# RiskChemi_Monitor_V1_05M1.net
KiCad netlist of a schematic drawn in Altium Designer
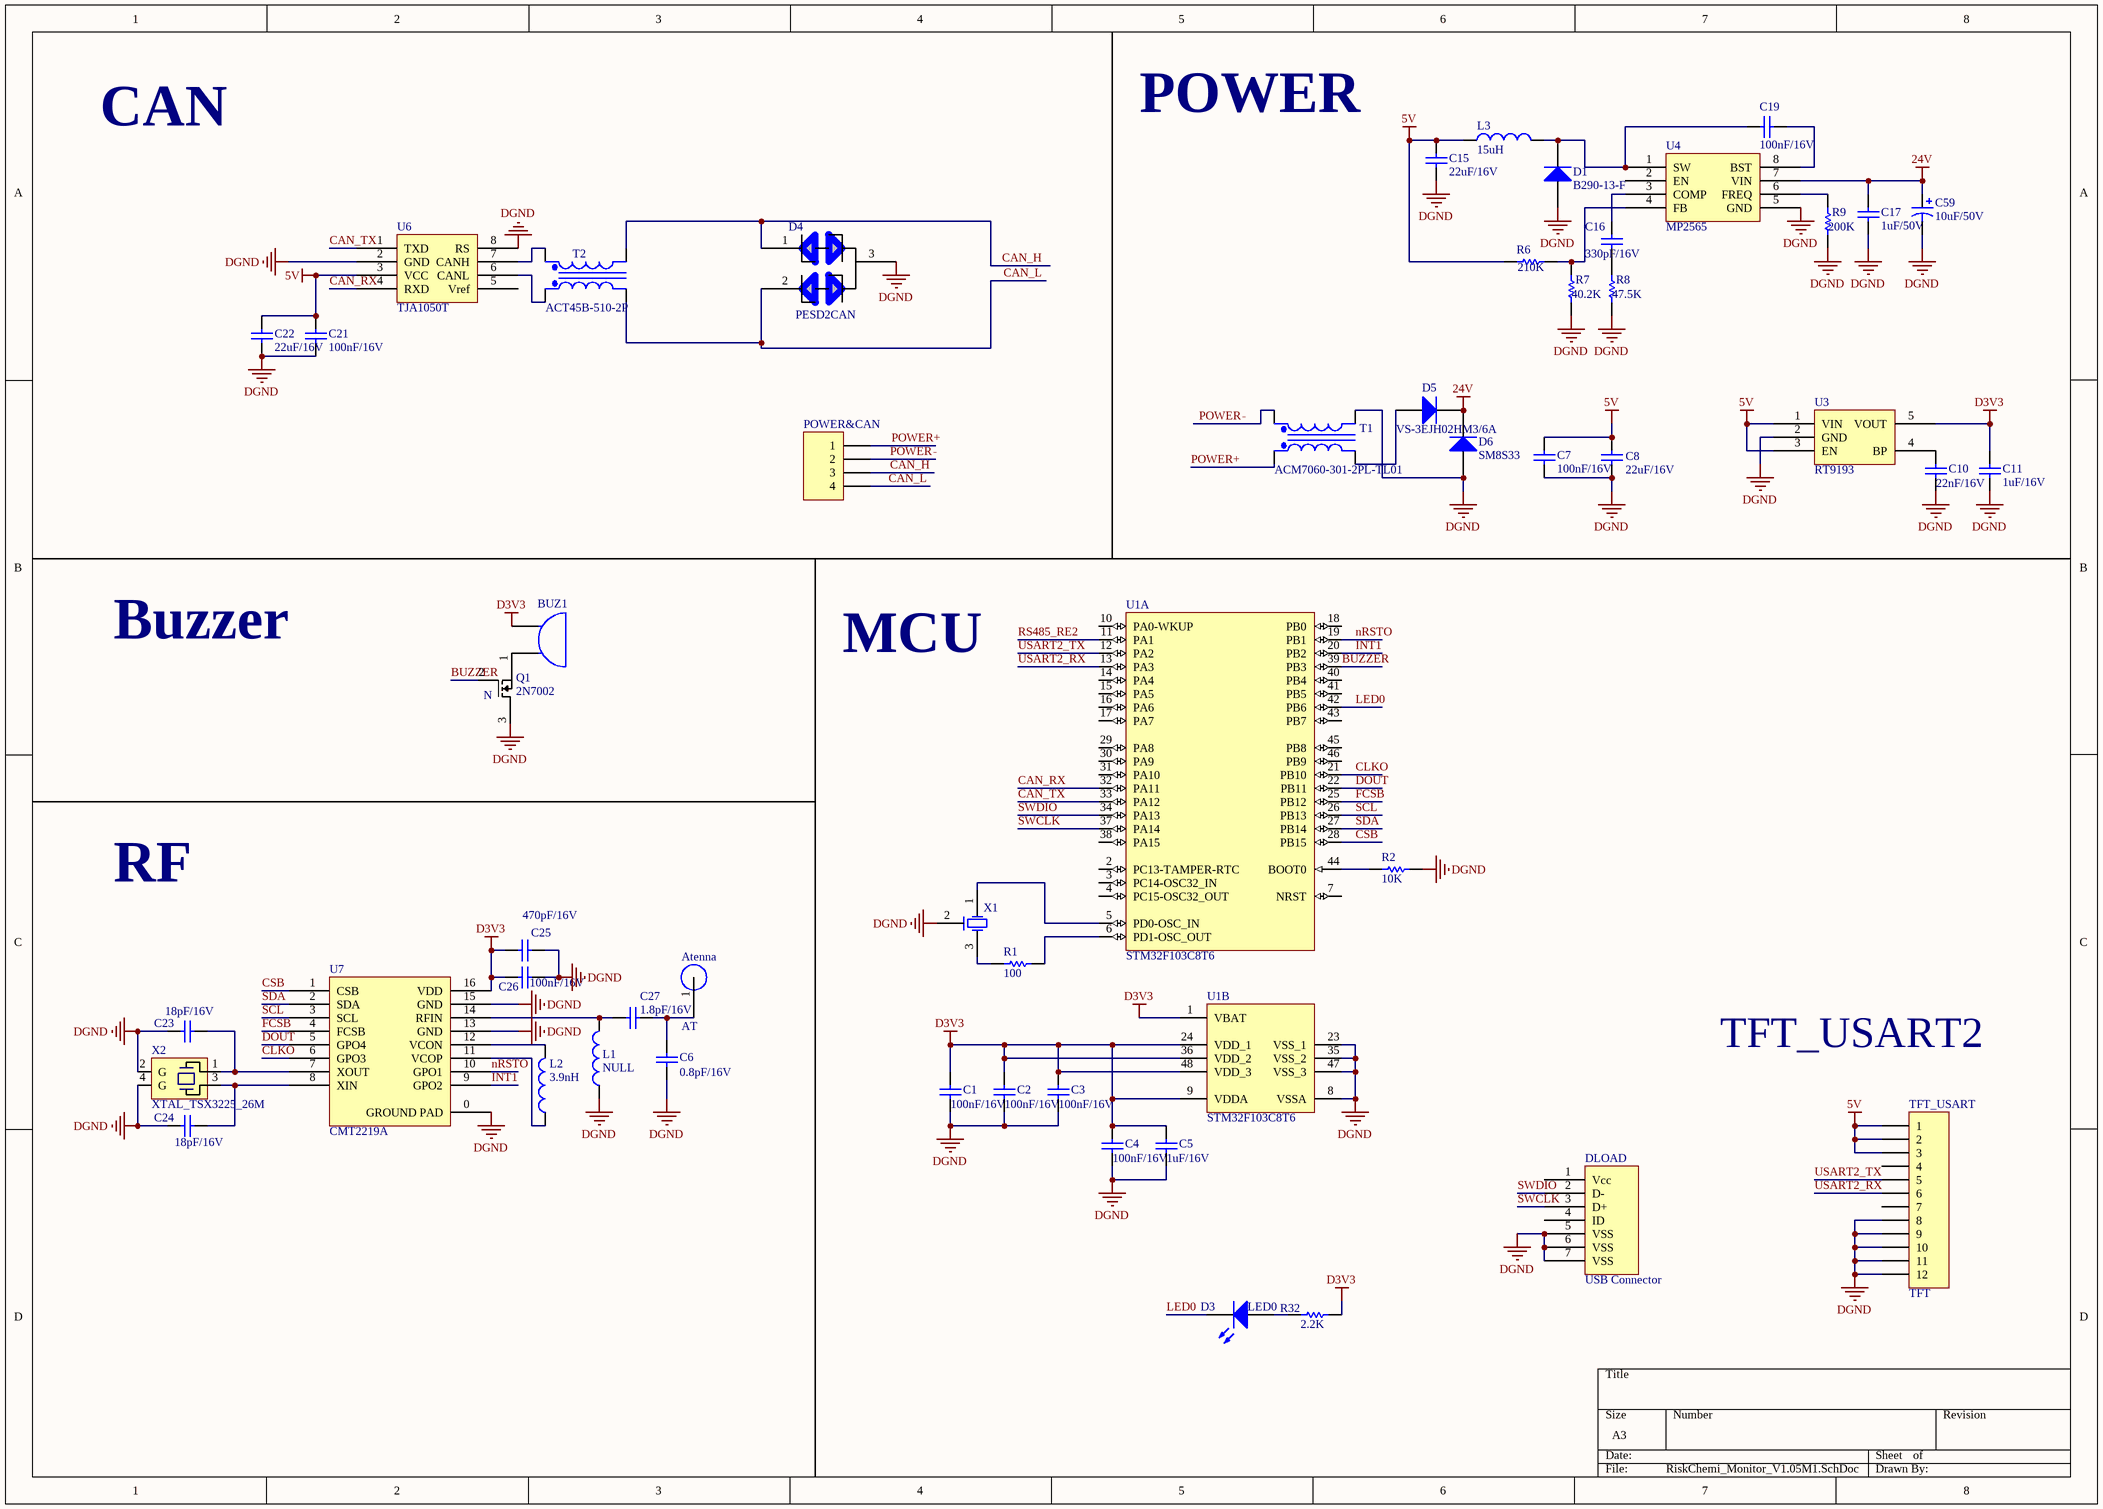
[diagram p0: RiskChemi_Monitor_V1.05M1.SchDoc]

(export (version "E")
  (design (tool "Eeschema 10.0.6"))
  (components
    (comp (ref "Atenna") (value "AT") (footprint "PIN1") (libsource (lib "MySchlib1") (part "AT")))
    (comp (ref "BUZ1")
      (value "BUZZER")
      (footprint "BUZ0905")
      (description "Buzzer")
      (libsource (lib "杂元件库") (part "BUZZER"))
    )
    (comp (ref "C1")
      (value "100nF/16V")
      (footprint "0603")
      (description "Capacitor")
      (fields (field (name "PUBLISHER") "Altium Limited"))
      (libsource (lib "Miscellaneous Devices") (part "Cap"))
    )
    (comp (ref "C2")
      (value "100nF/16V")
      (footprint "0603")
      (description "Capacitor")
      (fields (field (name "PUBLISHER") "Altium Limited"))
      (libsource (lib "Miscellaneous Devices") (part "Cap"))
    )
    (comp (ref "C3")
      (value "100nF/16V")
      (footprint "0603")
      (description "Capacitor")
      (fields (field (name "PUBLISHER") "Altium Limited"))
      (libsource (lib "Miscellaneous Devices") (part "Cap"))
    )
    (comp (ref "C4")
      (value "100nF/16V")
      (footprint "0603")
      (description "Capacitor")
      (fields (field (name "PUBLISHER") "Altium Limited"))
      (libsource (lib "Miscellaneous Devices") (part "Cap"))
    )
    (comp (ref "C5")
      (value "1uF/16V")
      (footprint "0603")
      (description "Capacitor")
      (fields (field (name "PUBLISHER") "Altium Limited"))
      (libsource (lib "Miscellaneous Devices") (part "Cap"))
    )
    (comp (ref "C6")
      (value "0.8pF/16V")
      (footprint "0402")
      (description "Capacitor (Semiconductor SIM Model)")
      (fields (field (name "Comment") "0.8pF/25V") (field (name "PUBLISHER") "Altium Limited"))
      (libsource (lib "Miscellaneous Devices") (part "Cap Semi"))
    )
    (comp (ref "C7")
      (value "100nF/16V")
      (footprint "0805")
      (description "Capacitor,100V")
      (fields (field (name "PUBLISHER") "Altium Limited"))
      (libsource (lib "Miscellaneous Devices") (part "Cap"))
    )
    (comp (ref "C8")
      (value "22uF/16V")
      (footprint "0805")
      (description "Capacitor")
      (fields (field (name "PUBLISHER") "Altium Limited"))
      (libsource (lib "Miscellaneous Devices") (part "Cap"))
    )
    (comp (ref "C10")
      (value "22nF/16V")
      (footprint "BinFeng:0603")
      (description "Capacitor")
      (fields (field (name "PUBLISHER") "Altium Limited"))
      (libsource (lib "Miscellaneous Devices") (part "Cap"))
    )
    (comp (ref "C11")
      (value "1uF/16V")
      (footprint "BinFeng:0603")
      (description "Capacitor")
      (fields (field (name "PUBLISHER") "Altium Limited"))
      (libsource (lib "Miscellaneous Devices") (part "Cap"))
    )
    (comp (ref "C15")
      (value "22uF/16V")
      (footprint "0805")
      (description "Capacitor,50V")
      (fields (field (name "PUBLISHER") "Altium Limited"))
      (libsource (lib "Miscellaneous Devices") (part "Cap"))
    )
    (comp (ref "C16")
      (value "330pF/16V")
      (footprint "BinFeng:0402")
      (description "Capacitor")
      (fields (field (name "PUBLISHER") "Altium Limited"))
      (libsource (lib "Miscellaneous Devices") (part "Cap"))
    )
    (comp (ref "C17")
      (value "1uF/50V")
      (footprint "0805")
      (description "Capacitor,100V")
      (fields (field (name "PUBLISHER") "Altium Limited"))
      (libsource (lib "Miscellaneous Devices") (part "Cap"))
    )
    (comp (ref "C19")
      (value "100nF/16V")
      (footprint "BinFeng:0402")
      (description "Capacitor")
      (fields (field (name "PUBLISHER") "Altium Limited"))
      (libsource (lib "Miscellaneous Devices") (part "Cap"))
    )
    (comp (ref "C21")
      (value "100nF/16V")
      (footprint "0603")
      (description "Capacitor")
      (fields (field (name "PUBLISHER") "Altium Limited"))
      (libsource (lib "Miscellaneous Devices") (part "Cap"))
    )
    (comp (ref "C22")
      (value "22uF/16V")
      (footprint "0805")
      (description "Capacitor")
      (fields (field (name "PUBLISHER") "Altium Limited"))
      (libsource (lib "Miscellaneous Devices") (part "Cap"))
    )
    (comp (ref "C23")
      (value "18pF/16V")
      (footprint "BinFeng:0402")
      (description "Capacitor")
      (fields (field (name "PUBLISHER") "Altium Limited"))
      (libsource (lib "Miscellaneous Devices") (part "Cap"))
    )
    (comp (ref "C24")
      (value "18pF/16V")
      (footprint "BinFeng:0402")
      (description "Capacitor")
      (fields (field (name "PUBLISHER") "Altium Limited"))
      (libsource (lib "Miscellaneous Devices") (part "Cap"))
    )
    (comp (ref "C25")
      (value "470pF/16V")
      (footprint "BinFeng:0402")
      (description "Capacitor")
      (fields (field (name "PUBLISHER") "Altium Limited"))
      (libsource (lib "Miscellaneous Devices") (part "Cap"))
    )
    (comp (ref "C26")
      (value "100nF/16V")
      (footprint "BinFeng:0603")
      (description "Capacitor")
      (fields (field (name "PUBLISHER") "Altium Limited"))
      (libsource (lib "Miscellaneous Devices") (part "Cap"))
    )
    (comp (ref "C27")
      (value "1.8pF/16V")
      (footprint "BinFeng:nosilk_0402")
      (description "Capacitor")
      (fields (field (name "PUBLISHER") "Altium Limited"))
      (libsource (lib "Miscellaneous Devices") (part "Cap"))
    )
    (comp (ref "C59")
      (value "10uF/50V")
      (footprint "6032_pol")
      (description "Polarized Capacitor (Radial)")
      (fields (field (name "PUBLISHER") "Altium Limited"))
      (libsource (lib "Miscellaneous Devices") (part "Cap Pol1"))
    )
    (comp (ref "D1")
      (value "B290-13-F")
      (footprint "back:B290")
      (description "Default Diode")
      (fields (field (name "PUBLISHER") "Altium Limited"))
      (libsource (lib "Miscellaneous Devices") (part "Diode"))
    )
    (comp (ref "D3")
      (value "LED0")
      (footprint "LED")
      (description "green LED")
      (fields (field (name "PUBLISHER") "Altium Limited"))
      (libsource (lib "Miscellaneous Devices") (part "LED0"))
    )
    (comp (ref "D4")
      (value "PESD2CAN")
      (footprint "SOT23")
      (libsource (lib "BinFeng_Connectors") (part "PESD1CAN"))
    )
    (comp (ref "D5")
      (value "VS-3EJH02HM3/6A")
      (footprint "back:B290")
      (description "1 Amp General Purpose Rectifier")
      (fields (field (name "PUBLISHER") "Altium Limited"))
      (libsource (lib "Miscellaneous Devices") (part "Diode 1N4007"))
    )
    (comp (ref "D6")
      (value "SM8S33")
      (footprint "SM8S")
      (description "1 Amp General Purpose Rectifier")
      (fields (field (name "PUBLISHER") "Altium Limited"))
      (libsource (lib "Miscellaneous Devices") (part "Diode 1N4007"))
    )
    (comp (ref "DLOAD")
      (value "USB Connector")
      (footprint "Mini_USB")
      (libsource (lib "BinFeng_Connectors") (part "Component_1"))
    )
    (comp (ref "L1")
      (value "NULL")
      (footprint "Miscellaneous Devices:0402")
      (description "Inductor")
      (fields (field (name "PUBLISHER") "Altium Limited"))
      (libsource (lib "Miscellaneous Devices") (part "Inductor"))
    )
    (comp (ref "L2")
      (value "3.9nH")
      (footprint "BinFeng:0603")
      (description "Inductor")
      (fields (field (name "PUBLISHER") "Altium Limited"))
      (libsource (lib "Miscellaneous Devices") (part "Inductor"))
    )
    (comp (ref "L3")
      (value "15uH")
      (footprint "4*4 Inductor")
      (description "Inductor, 1A")
      (fields (field (name "PUBLISHER") "Altium Limited"))
      (libsource (lib "Miscellaneous Devices") (part "Inductor"))
    )
    (comp (ref "POWER&CAN")
      (value "Header 4")
      (footprint "hg:Wafer 4pin")
      (description "Header, 4-Pin")
      (fields (field (name "PUBLISHER") "Altium Limited"))
      (libsource (lib "Miscellaneous Connectors") (part "Header 4"))
    )
    (comp (ref "Q1") (value "2N7002") (footprint "2N7002") (libsource (lib "seeder") (part "N-MOSFET")))
    (comp (ref "R1")
      (value "100")
      (footprint "back:0603")
      (description "Resistor")
      (fields (field (name "PUBLISHER") "Altium Limited"))
      (libsource (lib "Miscellaneous Devices") (part "Res1"))
    )
    (comp (ref "R2")
      (value "10K")
      (footprint "back:0603")
      (description "Resistor")
      (fields (field (name "PUBLISHER") "Altium Limited"))
      (libsource (lib "Miscellaneous Devices") (part "Res1"))
    )
    (comp (ref "R6")
      (value "210K")
      (footprint "BinFeng:0402")
      (description "Resistor")
      (fields (field (name "PUBLISHER") "Altium Limited"))
      (libsource (lib "Miscellaneous Devices") (part "Res1"))
    )
    (comp (ref "R7")
      (value "40.2K")
      (footprint "BinFeng:0402")
      (description "Resistor")
      (fields (field (name "PUBLISHER") "Altium Limited"))
      (libsource (lib "Miscellaneous Devices") (part "Res1"))
    )
    (comp (ref "R8")
      (value "47.5K")
      (footprint "BinFeng:0402")
      (description "Resistor")
      (fields (field (name "PUBLISHER") "Altium Limited"))
      (libsource (lib "Miscellaneous Devices") (part "Res1"))
    )
    (comp (ref "R9")
      (value "200K")
      (footprint "BinFeng:0402")
      (description "Resistor")
      (fields (field (name "PUBLISHER") "Altium Limited"))
      (libsource (lib "Miscellaneous Devices") (part "Res1"))
    )
    (comp (ref "R32")
      (value "2.2K")
      (footprint "BinFeng:0603")
      (description "Resistor")
      (fields (field (name "PUBLISHER") "Altium Limited"))
      (libsource (lib "Miscellaneous Devices") (part "Res1"))
    )
    (comp (ref "T1")
      (value "ACM7060-301-2PL-TL01")
      (footprint "ACM7060-301-2P-TL01")
      (description "Transformer (Equivalent Circuit Model)")
      (fields (field (name "PUBLISHER") "Altium Limited"))
      (libsource (lib "Miscellaneous Devices") (part "Trans Eq"))
    )
    (comp (ref "T2")
      (value "ACT45B-510-2P")
      (footprint "ACT45B-510-2P")
      (description "Transformer (Equivalent Circuit Model)")
      (fields (field (name "PUBLISHER") "Altium Limited"))
      (libsource (lib "Miscellaneous Devices") (part "Trans Eq"))
    )
    (comp (ref "TFT_USART")
      (value "TFT")
      (footprint "FCC_10pin_1mm")
      (description "Header, 12-Pin")
      (fields (field (name "PUBLISHER") "Altium Limited"))
      (libsource (lib "Miscellaneous Connectors") (part "Header 12"))
    )
    (comp (ref "U1")
      (value "STM32F103C8T6")
      (footprint "STM-LQFP48_N")
      (libsource (lib "STMicroelectronics STM32 F1") (part "STM32F103C8T6"))
    )
    (comp (ref "U3") (value "RT9193") (footprint "SOT-23-5") (libsource (lib "BinFeng_IC") (part "RT9193")))
    (comp (ref "U4")
      (value "MP2565")
      (footprint "SO8")
      (description "DCDC 4.5V~28V input 1.8V ~5V output low power")
      (libsource (lib "BinFeng_IC") (part "MP1584"))
    )
    (comp (ref "U6")
      (value "TJA1050T")
      (footprint "SO8")
      (description "CAN Tranceiver")
      (libsource (lib "BinFeng_IC") (part "TJA1050T"))
    )
    (comp (ref "U7")
      (value "CMT2219A")
      (footprint "back:QFN16")
      (libsource (lib "BinFeng_IC") (part "CMT2219A"))
    )
    (comp (ref "X1") (value "8M smd") (footprint "8Mhz_XTAL") (libsource (lib "Schlib1") (part "8M smd")))
    (comp (ref "X2")
      (value "XTAL_TSX3225_26M")
      (footprint "XTAL3225")
      (libsource (lib "BinFeng_IC") (part "XTAL_Negative"))
    )
  )
  (nets
    (net (code "1") (name "/BUZZER") (class "Default")
      (node (ref "Q1") (pin "2") (pinfunction "G_2") (pintype "passive"))
      (node (ref "U1") (pin "39") (pinfunction "PB3_39") (pintype "bidirectional"))
    )
    (net (code "2") (name "/CAN_H") (class "Default")
      (node (ref "D4") (pin "1") (pinfunction "11_1") (pintype "passive"))
      (node (ref "POWER&CAN") (pin "3") (pinfunction "3_3") (pintype "passive"))
      (node (ref "T2") (pin "4") (pinfunction "Sec-_4") (pintype "passive"))
    )
    (net (code "3") (name "/CAN_L") (class "Default")
      (node (ref "D4") (pin "2") (pinfunction "12_2") (pintype "passive"))
      (node (ref "POWER&CAN") (pin "4") (pinfunction "4_4") (pintype "passive"))
      (node (ref "T2") (pin "2") (pinfunction "Pri-_2") (pintype "passive"))
    )
    (net (code "4") (name "/CAN_RX") (class "Default")
      (node (ref "U1") (pin "32") (pinfunction "PA11_32") (pintype "bidirectional"))
      (node (ref "U6") (pin "4") (pinfunction "RXD_4") (pintype "passive"))
    )
    (net (code "5") (name "/CAN_TX") (class "Default")
      (node (ref "U1") (pin "33") (pinfunction "PA12_33") (pintype "bidirectional"))
      (node (ref "U6") (pin "1") (pinfunction "TXD_1") (pintype "passive"))
    )
    (net (code "6") (name "/CLKO") (class "Default")
      (node (ref "U1") (pin "21") (pinfunction "PB10_21") (pintype "bidirectional"))
      (node (ref "U7") (pin "6") (pinfunction "GPO3_6") (pintype "passive"))
    )
    (net (code "7") (name "/CSB") (class "Default")
      (node (ref "U1") (pin "28") (pinfunction "PB15_28") (pintype "bidirectional"))
      (node (ref "U7") (pin "1") (pinfunction "CSB_1") (pintype "passive"))
    )
    (net (code "8") (name "/DOUT") (class "Default")
      (node (ref "U1") (pin "22") (pinfunction "PB11_22") (pintype "bidirectional"))
      (node (ref "U7") (pin "5") (pinfunction "GPO4_5") (pintype "passive"))
    )
    (net (code "9") (name "/FCSB") (class "Default")
      (node (ref "U1") (pin "25") (pinfunction "PB12_25") (pintype "bidirectional"))
      (node (ref "U7") (pin "4") (pinfunction "FCSB_4") (pintype "passive"))
    )
    (net (code "10") (name "/INT1") (class "Default")
      (node (ref "U1") (pin "20") (pinfunction "PB2_20") (pintype "bidirectional"))
      (node (ref "U7") (pin "9") (pinfunction "GPO2_9") (pintype "passive"))
    )
    (net (code "11") (name "/LED0") (class "Default")
      (node (ref "D3") (pin "2") (pinfunction "K_2") (pintype "passive"))
      (node (ref "U1") (pin "42") (pinfunction "PB6_42") (pintype "bidirectional"))
    )
    (net (code "12") (name "/POWER+") (class "Default")
      (node (ref "POWER&CAN") (pin "1") (pinfunction "1_1") (pintype "passive"))
      (node (ref "T1") (pin "1") (pinfunction "Pri+_1") (pintype "passive"))
    )
    (net (code "13") (name "/POWER﹣") (class "Default")
      (node (ref "POWER&CAN") (pin "2") (pinfunction "2_2") (pintype "passive"))
      (node (ref "T1") (pin "3") (pinfunction "Sec+_3") (pintype "passive"))
    )
    (net (code "14") (name "/RS485_RE2") (class "Default")
      (node (ref "U1") (pin "11") (pinfunction "PA1_11") (pintype "bidirectional"))
    )
    (net (code "15") (name "/SCL") (class "Default")
      (node (ref "U1") (pin "26") (pinfunction "PB13_26") (pintype "bidirectional"))
      (node (ref "U7") (pin "3") (pinfunction "SCL_3") (pintype "passive"))
    )
    (net (code "16") (name "/SDA") (class "Default")
      (node (ref "U1") (pin "27") (pinfunction "PB14_27") (pintype "bidirectional"))
      (node (ref "U7") (pin "2") (pinfunction "SDA_2") (pintype "passive"))
    )
    (net (code "17") (name "/SWCLK") (class "Default")
      (node (ref "DLOAD") (pin "3") (pinfunction "D+_3") (pintype "passive"))
      (node (ref "U1") (pin "37") (pinfunction "PA14_37") (pintype "bidirectional"))
    )
    (net (code "18") (name "/SWDIO") (class "Default")
      (node (ref "DLOAD") (pin "2") (pinfunction "D-_2") (pintype "passive"))
      (node (ref "U1") (pin "34") (pinfunction "PA13_34") (pintype "bidirectional"))
    )
    (net (code "19") (name "/USART2_RX") (class "Default")
      (node (ref "TFT_USART") (pin "6") (pinfunction "6_6") (pintype "passive"))
      (node (ref "U1") (pin "13") (pinfunction "PA3_13") (pintype "bidirectional"))
    )
    (net (code "20") (name "/USART2_TX") (class "Default")
      (node (ref "TFT_USART") (pin "5") (pinfunction "5_5") (pintype "passive"))
      (node (ref "U1") (pin "12") (pinfunction "PA2_12") (pintype "bidirectional"))
    )
    (net (code "21") (name "/nRSTO") (class "Default")
      (node (ref "U1") (pin "19") (pinfunction "PB1_19") (pintype "bidirectional"))
      (node (ref "U7") (pin "10") (pinfunction "GPO1_10") (pintype "passive"))
    )
    (net (code "22") (name "5V") (class "Default")
      (node (ref "C15") (pin "2") (pinfunction "2_2") (pintype "passive"))
      (node (ref "C21") (pin "1") (pinfunction "1_1") (pintype "passive"))
      (node (ref "C22") (pin "2") (pinfunction "2_2") (pintype "passive"))
      (node (ref "C7") (pin "2") (pinfunction "2_2") (pintype "passive"))
      (node (ref "C8") (pin "2") (pinfunction "2_2") (pintype "passive"))
      (node (ref "L3") (pin "1") (pinfunction "1_1") (pintype "passive"))
      (node (ref "R6") (pin "2") (pinfunction "2_2") (pintype "passive"))
      (node (ref "TFT_USART") (pin "1") (pinfunction "1_1") (pintype "passive"))
      (node (ref "TFT_USART") (pin "2") (pinfunction "2_2") (pintype "passive"))
      (node (ref "TFT_USART") (pin "3") (pinfunction "3_3") (pintype "passive"))
      (node (ref "U3") (pin "1") (pinfunction "VIN_1") (pintype "passive"))
      (node (ref "U3") (pin "3") (pinfunction "EN_3") (pintype "passive"))
      (node (ref "U6") (pin "3") (pinfunction "VCC_3") (pintype "passive"))
    )
    (net (code "23") (name "24V") (class "Default")
      (node (ref "C17") (pin "2") (pinfunction "2_2") (pintype "passive"))
      (node (ref "C59") (pin "1") (pinfunction "1_1") (pintype "passive"))
      (node (ref "D5") (pin "2") (pinfunction "K_2") (pintype "passive"))
      (node (ref "D6") (pin "2") (pinfunction "K_2") (pintype "passive"))
      (node (ref "U4") (pin "7") (pinfunction "VIN_7") (pintype "passive"))
    )
    (net (code "24") (name "D3V3") (class "Default")
      (node (ref "BUZ1") (pin "1") (pinfunction "A_1") (pintype "passive"))
      (node (ref "C1") (pin "2") (pinfunction "2_2") (pintype "passive"))
      (node (ref "C11") (pin "2") (pinfunction "2_2") (pintype "passive"))
      (node (ref "C2") (pin "2") (pinfunction "2_2") (pintype "passive"))
      (node (ref "C25") (pin "2") (pinfunction "2_2") (pintype "passive"))
      (node (ref "C26") (pin "2") (pinfunction "2_2") (pintype "passive"))
      (node (ref "C3") (pin "2") (pinfunction "2_2") (pintype "passive"))
      (node (ref "C4") (pin "2") (pinfunction "2_2") (pintype "passive"))
      (node (ref "C5") (pin "2") (pinfunction "2_2") (pintype "passive"))
      (node (ref "R32") (pin "1") (pinfunction "1_1") (pintype "passive"))
      (node (ref "U1") (pin "1") (pinfunction "VBAT_1") (pintype "power_in"))
      (node (ref "U1") (pin "24") (pinfunction "VDD_1_24") (pintype "power_in"))
      (node (ref "U1") (pin "36") (pinfunction "VDD_2_36") (pintype "power_in"))
      (node (ref "U1") (pin "48") (pinfunction "VDD_3_48") (pintype "power_in"))
      (node (ref "U1") (pin "9") (pinfunction "VDDA_9") (pintype "power_in"))
      (node (ref "U3") (pin "5") (pinfunction "VOUT_5") (pintype "passive"))
      (node (ref "U7") (pin "16") (pinfunction "VDD_16") (pintype "passive"))
    )
    (net (code "25") (name "DGND") (class "Default")
      (node (ref "C1") (pin "1") (pinfunction "1_1") (pintype "passive"))
      (node (ref "C10") (pin "1") (pinfunction "1_1") (pintype "passive"))
      (node (ref "C11") (pin "1") (pinfunction "1_1") (pintype "passive"))
      (node (ref "C15") (pin "1") (pinfunction "1_1") (pintype "passive"))
      (node (ref "C17") (pin "1") (pinfunction "1_1") (pintype "passive"))
      (node (ref "C2") (pin "1") (pinfunction "1_1") (pintype "passive"))
      (node (ref "C21") (pin "2") (pinfunction "2_2") (pintype "passive"))
      (node (ref "C22") (pin "1") (pinfunction "1_1") (pintype "passive"))
      (node (ref "C23") (pin "2") (pinfunction "2_2") (pintype "passive"))
      (node (ref "C24") (pin "2") (pinfunction "2_2") (pintype "passive"))
      (node (ref "C25") (pin "1") (pinfunction "1_1") (pintype "passive"))
      (node (ref "C26") (pin "1") (pinfunction "1_1") (pintype "passive"))
      (node (ref "C3") (pin "1") (pinfunction "1_1") (pintype "passive"))
      (node (ref "C4") (pin "1") (pinfunction "1_1") (pintype "passive"))
      (node (ref "C5") (pin "1") (pinfunction "1_1") (pintype "passive"))
      (node (ref "C59") (pin "2") (pinfunction "2_2") (pintype "passive"))
      (node (ref "C6") (pin "1") (pinfunction "1_1") (pintype "passive"))
      (node (ref "C7") (pin "1") (pinfunction "1_1") (pintype "passive"))
      (node (ref "C8") (pin "1") (pinfunction "1_1") (pintype "passive"))
      (node (ref "D1") (pin "1") (pinfunction "A_1") (pintype "passive"))
      (node (ref "D4") (pin "3") (pinfunction "13_3") (pintype "passive"))
      (node (ref "D6") (pin "1") (pinfunction "A_1") (pintype "passive"))
      (node (ref "DLOAD") (pin "5") (pinfunction "VSS_5") (pintype "passive"))
      (node (ref "DLOAD") (pin "6") (pinfunction "VSS_6") (pintype "passive"))
      (node (ref "DLOAD") (pin "7") (pinfunction "VSS_7") (pintype "passive"))
      (node (ref "L1") (pin "1") (pinfunction "1_1") (pintype "passive"))
      (node (ref "Q1") (pin "3") (pinfunction "S_3") (pintype "passive"))
      (node (ref "R2") (pin "2") (pinfunction "2_2") (pintype "passive"))
      (node (ref "R7") (pin "1") (pinfunction "1_1") (pintype "passive"))
      (node (ref "R8") (pin "1") (pinfunction "1_1") (pintype "passive"))
      (node (ref "R9") (pin "1") (pinfunction "1_1") (pintype "passive"))
      (node (ref "T1") (pin "4") (pinfunction "Sec-_4") (pintype "passive"))
      (node (ref "TFT_USART") (pin "10") (pinfunction "10_10") (pintype "passive"))
      (node (ref "TFT_USART") (pin "11") (pinfunction "11_11") (pintype "passive"))
      (node (ref "TFT_USART") (pin "12") (pinfunction "12_12") (pintype "passive"))
      (node (ref "TFT_USART") (pin "8") (pinfunction "8_8") (pintype "passive"))
      (node (ref "TFT_USART") (pin "9") (pinfunction "9_9") (pintype "passive"))
      (node (ref "U1") (pin "23") (pinfunction "VSS_1_23") (pintype "power_in"))
      (node (ref "U1") (pin "35") (pinfunction "VSS_2_35") (pintype "power_in"))
      (node (ref "U1") (pin "47") (pinfunction "VSS_3_47") (pintype "power_in"))
      (node (ref "U1") (pin "8") (pinfunction "VSSA_8") (pintype "power_in"))
      (node (ref "U3") (pin "2") (pinfunction "GND_2") (pintype "passive"))
      (node (ref "U4") (pin "5") (pinfunction "GND_5") (pintype "passive"))
      (node (ref "U6") (pin "2") (pinfunction "GND_2") (pintype "passive"))
      (node (ref "U6") (pin "8") (pinfunction "RS_8") (pintype "passive"))
      (node (ref "U7") (pin "0") (pinfunction "GROUND_PAD_0") (pintype "passive"))
      (node (ref "U7") (pin "13") (pinfunction "GND_13") (pintype "passive"))
      (node (ref "U7") (pin "15") (pinfunction "GND_15") (pintype "passive"))
      (node (ref "X1") (pin "2") (pinfunction "GND_2") (pintype "passive"))
      (node (ref "X2") (pin "2") (pinfunction "G_2") (pintype "passive"))
      (node (ref "X2") (pin "4") (pinfunction "G_4") (pintype "passive"))
    )
    (net (code "26") (name "Net-(Atenna-Pad1)") (class "Default")
      (node (ref "Atenna") (pin "1") (pinfunction "1_1") (pintype "passive"))
      (node (ref "C27") (pin "1") (pinfunction "1_1") (pintype "passive"))
      (node (ref "C6") (pin "2") (pinfunction "2_2") (pintype "passive"))
    )
    (net (code "27") (name "Net-(BUZ1-B)") (class "Default")
      (node (ref "BUZ1") (pin "2") (pinfunction "B_2") (pintype "passive"))
      (node (ref "Q1") (pin "1") (pinfunction "D_1") (pintype "passive"))
    )
    (net (code "28") (name "Net-(C16-Pad2)") (class "Default")
      (node (ref "C16") (pin "2") (pinfunction "2_2") (pintype "passive"))
      (node (ref "R8") (pin "2") (pinfunction "2_2") (pintype "passive"))
    )
    (net (code "29") (name "Net-(D1-K)") (class "Default")
      (node (ref "C19") (pin "2") (pinfunction "2_2") (pintype "passive"))
      (node (ref "D1") (pin "2") (pinfunction "K_2") (pintype "passive"))
      (node (ref "L3") (pin "2") (pinfunction "2_2") (pintype "passive"))
      (node (ref "U4") (pin "1") (pinfunction "SW_1") (pintype "passive"))
    )
    (net (code "30") (name "Net-(D3-A)") (class "Default")
      (node (ref "D3") (pin "1") (pinfunction "A_1") (pintype "passive"))
      (node (ref "R32") (pin "2") (pinfunction "2_2") (pintype "passive"))
    )
    (net (code "31") (name "Net-(D5-A)") (class "Default")
      (node (ref "D5") (pin "1") (pinfunction "A_1") (pintype "passive"))
      (node (ref "T1") (pin "2") (pinfunction "Pri-_2") (pintype "passive"))
    )
    (net (code "32") (name "Net-(T2-Pri+)") (class "Default")
      (node (ref "T2") (pin "1") (pinfunction "Pri+_1") (pintype "passive"))
      (node (ref "U6") (pin "6") (pinfunction "CANL_6") (pintype "passive"))
    )
    (net (code "33") (name "Net-(T2-Sec+)") (class "Default")
      (node (ref "T2") (pin "3") (pinfunction "Sec+_3") (pintype "passive"))
      (node (ref "U6") (pin "7") (pinfunction "CANH_7") (pintype "passive"))
    )
    (net (code "34") (name "Net-(U1A-BOOT0)") (class "Default")
      (node (ref "R2") (pin "1") (pinfunction "1_1") (pintype "passive"))
      (node (ref "U1") (pin "44") (pinfunction "BOOT0_44") (pintype "input"))
    )
    (net (code "35") (name "Net-(U1A-PD0-OSC_IN)") (class "Default")
      (node (ref "U1") (pin "5") (pinfunction "PD0-OSC_IN_5") (pintype "bidirectional"))
      (node (ref "X1") (pin "1") (pinfunction "OSC1_1") (pintype "passive"))
    )
    (net (code "36") (name "Net-(U1A-PD1-OSC_OUT)") (class "Default")
      (node (ref "R1") (pin "2") (pinfunction "2_2") (pintype "passive"))
      (node (ref "U1") (pin "6") (pinfunction "PD1-OSC_OUT_6") (pintype "bidirectional"))
    )
    (net (code "37") (name "Net-(U3-BP)") (class "Default")
      (node (ref "C10") (pin "2") (pinfunction "2_2") (pintype "passive"))
      (node (ref "U3") (pin "4") (pinfunction "BP_4") (pintype "passive"))
    )
    (net (code "38") (name "Net-(U4-BST)") (class "Default")
      (node (ref "C19") (pin "1") (pinfunction "1_1") (pintype "passive"))
      (node (ref "U4") (pin "8") (pinfunction "BST_8") (pintype "passive"))
    )
    (net (code "39") (name "Net-(U4-COMP)") (class "Default")
      (node (ref "C16") (pin "1") (pinfunction "1_1") (pintype "passive"))
      (node (ref "U4") (pin "3") (pinfunction "COMP_3") (pintype "passive"))
    )
    (net (code "40") (name "Net-(U4-FB)") (class "Default")
      (node (ref "R6") (pin "1") (pinfunction "1_1") (pintype "passive"))
      (node (ref "R7") (pin "2") (pinfunction "2_2") (pintype "passive"))
      (node (ref "U4") (pin "4") (pinfunction "FB_4") (pintype "passive"))
    )
    (net (code "41") (name "Net-(U4-FREQ)") (class "Default")
      (node (ref "R9") (pin "2") (pinfunction "2_2") (pintype "passive"))
      (node (ref "U4") (pin "6") (pinfunction "FREQ_6") (pintype "passive"))
    )
    (net (code "42") (name "Net-(U7-RFIN)") (class "Default")
      (node (ref "C27") (pin "2") (pinfunction "2_2") (pintype "passive"))
      (node (ref "L1") (pin "2") (pinfunction "2_2") (pintype "passive"))
      (node (ref "U7") (pin "14") (pinfunction "RFIN_14") (pintype "passive"))
    )
    (net (code "43") (name "Net-(U7-VCON)") (class "Default")
      (node (ref "L2") (pin "2") (pinfunction "2_2") (pintype "passive"))
      (node (ref "U7") (pin "12") (pinfunction "VCON_12") (pintype "passive"))
    )
    (net (code "44") (name "Net-(U7-VCOP)") (class "Default")
      (node (ref "L2") (pin "1") (pinfunction "1_1") (pintype "passive"))
      (node (ref "U7") (pin "11") (pinfunction "VCOP_11") (pintype "passive"))
    )
    (net (code "45") (name "Net-(U7-XIN)") (class "Default")
      (node (ref "C24") (pin "1") (pinfunction "1_1") (pintype "passive"))
      (node (ref "U7") (pin "8") (pinfunction "XIN_8") (pintype "passive"))
      (node (ref "X2") (pin "3") (pintype "passive"))
    )
    (net (code "46") (name "Net-(U7-XOUT)") (class "Default")
      (node (ref "C23") (pin "1") (pinfunction "1_1") (pintype "passive"))
      (node (ref "U7") (pin "7") (pinfunction "XOUT_7") (pintype "passive"))
      (node (ref "X2") (pin "1") (pintype "passive"))
    )
    (net (code "47") (name "Net-(X1-OSC2)") (class "Default")
      (node (ref "R1") (pin "1") (pinfunction "1_1") (pintype "passive"))
      (node (ref "X1") (pin "3") (pinfunction "OSC2_3") (pintype "passive"))
    )
    (net (code "48") (name "unconnected-(DLOAD-ID-Pad4)") (class "Default")
      (node (ref "DLOAD") (pin "4") (pinfunction "ID_4") (pintype "passive"))
    )
    (net (code "49") (name "unconnected-(DLOAD-Vcc-Pad1)") (class "Default")
      (node (ref "DLOAD") (pin "1") (pinfunction "Vcc_1") (pintype "passive"))
    )
    (net (code "50") (name "unconnected-(TFT_USART-Pad4)") (class "Default")
      (node (ref "TFT_USART") (pin "4") (pinfunction "4_4") (pintype "passive"))
    )
    (net (code "51") (name "unconnected-(TFT_USART-Pad7)") (class "Default")
      (node (ref "TFT_USART") (pin "7") (pinfunction "7_7") (pintype "passive"))
    )
    (net (code "52") (name "unconnected-(U1A-NRST-Pad7)") (class "Default")
      (node (ref "U1") (pin "7") (pinfunction "NRST_7") (pintype "bidirectional"))
    )
    (net (code "53") (name "unconnected-(U1A-PA0-WKUP-Pad10)") (class "Default")
      (node (ref "U1") (pin "10") (pinfunction "PA0-WKUP_10") (pintype "bidirectional"))
    )
    (net (code "54") (name "unconnected-(U1A-PA4-Pad14)") (class "Default")
      (node (ref "U1") (pin "14") (pinfunction "PA4_14") (pintype "bidirectional"))
    )
    (net (code "55") (name "unconnected-(U1A-PA5-Pad15)") (class "Default")
      (node (ref "U1") (pin "15") (pinfunction "PA5_15") (pintype "bidirectional"))
    )
    (net (code "56") (name "unconnected-(U1A-PA6-Pad16)") (class "Default")
      (node (ref "U1") (pin "16") (pinfunction "PA6_16") (pintype "bidirectional"))
    )
    (net (code "57") (name "unconnected-(U1A-PA7-Pad17)") (class "Default")
      (node (ref "U1") (pin "17") (pinfunction "PA7_17") (pintype "bidirectional"))
    )
    (net (code "58") (name "unconnected-(U1A-PA8-Pad29)") (class "Default")
      (node (ref "U1") (pin "29") (pinfunction "PA8_29") (pintype "bidirectional"))
    )
    (net (code "59") (name "unconnected-(U1A-PA9-Pad30)") (class "Default")
      (node (ref "U1") (pin "30") (pinfunction "PA9_30") (pintype "bidirectional"))
    )
    (net (code "60") (name "unconnected-(U1A-PA10-Pad31)") (class "Default")
      (node (ref "U1") (pin "31") (pinfunction "PA10_31") (pintype "bidirectional"))
    )
    (net (code "61") (name "unconnected-(U1A-PA15-Pad38)") (class "Default")
      (node (ref "U1") (pin "38") (pinfunction "PA15_38") (pintype "bidirectional"))
    )
    (net (code "62") (name "unconnected-(U1A-PB0-Pad18)") (class "Default")
      (node (ref "U1") (pin "18") (pinfunction "PB0_18") (pintype "bidirectional"))
    )
    (net (code "63") (name "unconnected-(U1A-PB4-Pad40)") (class "Default")
      (node (ref "U1") (pin "40") (pinfunction "PB4_40") (pintype "bidirectional"))
    )
    (net (code "64") (name "unconnected-(U1A-PB5-Pad41)") (class "Default")
      (node (ref "U1") (pin "41") (pinfunction "PB5_41") (pintype "bidirectional"))
    )
    (net (code "65") (name "unconnected-(U1A-PB7-Pad43)") (class "Default")
      (node (ref "U1") (pin "43") (pinfunction "PB7_43") (pintype "bidirectional"))
    )
    (net (code "66") (name "unconnected-(U1A-PB8-Pad45)") (class "Default")
      (node (ref "U1") (pin "45") (pinfunction "PB8_45") (pintype "bidirectional"))
    )
    (net (code "67") (name "unconnected-(U1A-PB9-Pad46)") (class "Default")
      (node (ref "U1") (pin "46") (pinfunction "PB9_46") (pintype "bidirectional"))
    )
    (net (code "68") (name "unconnected-(U1A-PC13-TAMPER-RTC-Pad2)") (class "Default")
      (node (ref "U1") (pin "2") (pinfunction "PC13-TAMPER-RTC_2") (pintype "bidirectional"))
    )
    (net (code "69") (name "unconnected-(U1A-PC14-OSC32_IN-Pad3)") (class "Default")
      (node (ref "U1") (pin "3") (pinfunction "PC14-OSC32_IN_3") (pintype "bidirectional"))
    )
    (net (code "70") (name "unconnected-(U1A-PC15-OSC32_OUT-Pad4)") (class "Default")
      (node (ref "U1") (pin "4") (pinfunction "PC15-OSC32_OUT_4") (pintype "bidirectional"))
    )
    (net (code "71") (name "unconnected-(U4-EN-Pad2)") (class "Default")
      (node (ref "U4") (pin "2") (pinfunction "EN_2") (pintype "passive"))
    )
    (net (code "72") (name "unconnected-(U6-Vref-Pad5)") (class "Default")
      (node (ref "U6") (pin "5") (pinfunction "Vref_5") (pintype "passive"))
    )
  )
)
